# thermostat.net
KiCad netlist of a schematic drawn in EAGLE
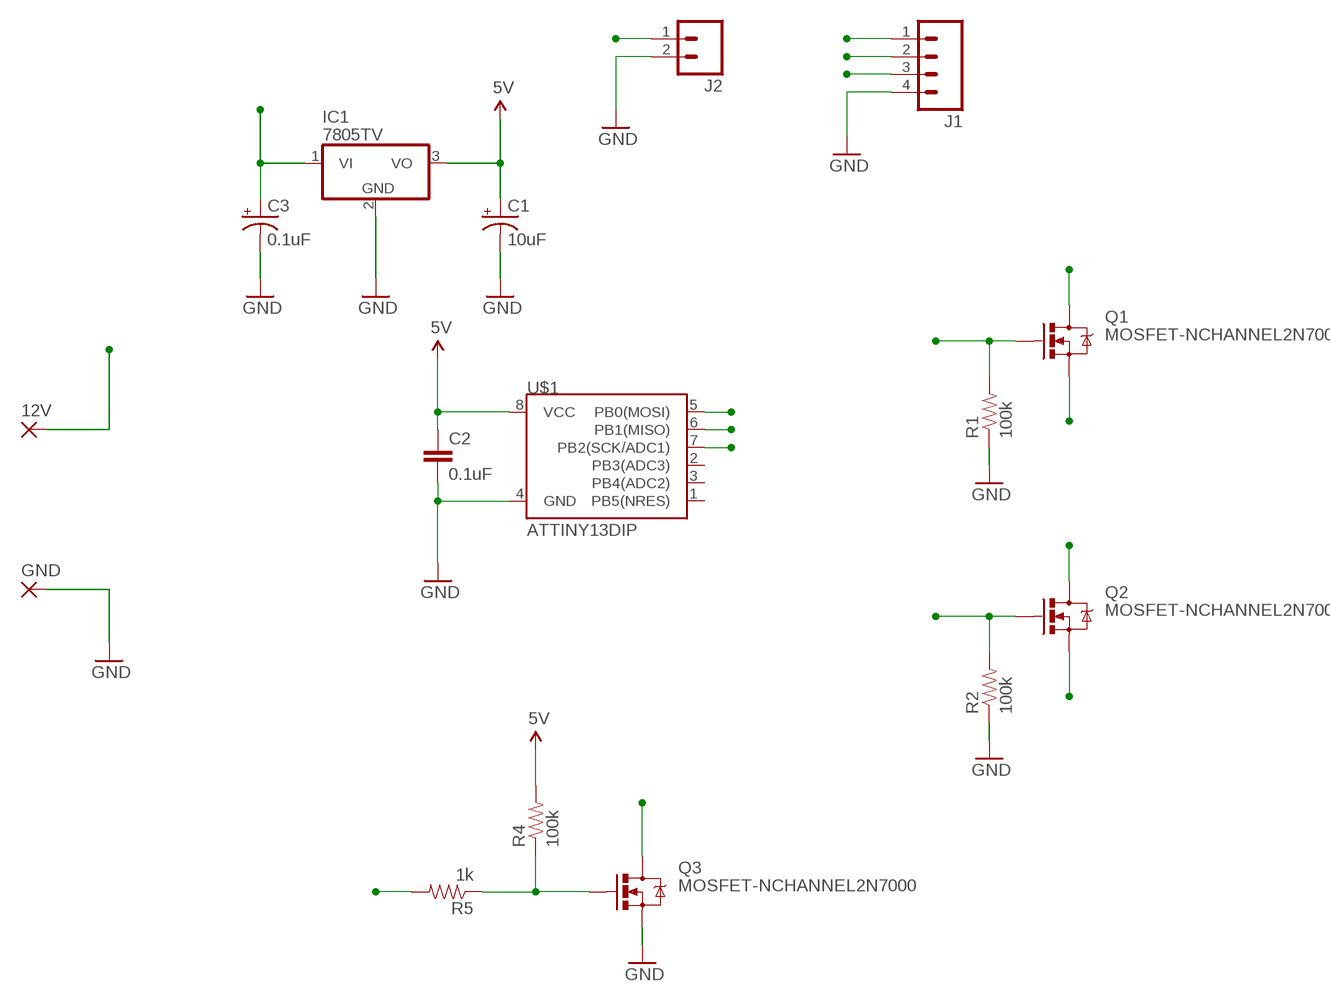
[diagram p0: schematic, sheet 1]

(export (version "E")
  (design (tool "Eeschema 10.0.6"))
  (components
    (comp (ref "12V")
      (value "WIREPAD2,54/0,8")
      (footprint "eagle-import:2,54_0,8")
      (libsource (lib "eagle-import") (part "WIREPAD2,54/0,8"))
    )
    (comp (ref "C1")
      (value "10uF")
      (footprint "eagle-import:CPOL-RADIAL-10UF-25V")
      (libsource (lib "eagle-import") (part "CAP_POLPTH2"))
    )
    (comp (ref "C2")
      (value "0.1uF")
      (footprint "eagle-import:CAP-PTH-SMALLEZ")
      (libsource (lib "eagle-import") (part "CAPEZ"))
    )
    (comp (ref "C3")
      (value "0.1uF")
      (footprint "eagle-import:CPOL-RADIAL-10UF-25V")
      (libsource (lib "eagle-import") (part "CAP_POLPTH2"))
    )
    (comp (ref "GND")
      (value "WIREPAD2,54/0,8")
      (footprint "eagle-import:2,54_0,8")
      (libsource (lib "eagle-import") (part "WIREPAD2,54/0,8"))
    )
    (comp (ref "IC1")
      (value "7805TV")
      (footprint "eagle-import:TO220V")
      (libsource (lib "eagle-import") (part "78TV05"))
    )
    (comp (ref "J1")
      (value "M04PTH")
      (footprint "eagle-import:1X04")
      (libsource (lib "eagle-import") (part "M04PTH"))
    )
    (comp (ref "J2")
      (value "M02PTH")
      (footprint "eagle-import:1X02")
      (libsource (lib "eagle-import") (part "M02PTH"))
    )
    (comp (ref "Q1")
      (value "MOSFET-NCHANNEL2N7000")
      (footprint "eagle-import:TO-92")
      (libsource (lib "eagle-import") (part "MOSFET-NCHANNEL2N7000"))
    )
    (comp (ref "Q2")
      (value "MOSFET-NCHANNEL2N7000")
      (footprint "eagle-import:TO-92")
      (libsource (lib "eagle-import") (part "MOSFET-NCHANNEL2N7000"))
    )
    (comp (ref "Q3")
      (value "MOSFET-NCHANNEL2N7000")
      (footprint "eagle-import:TO-92")
      (libsource (lib "eagle-import") (part "MOSFET-NCHANNEL2N7000"))
    )
    (comp (ref "R1")
      (value "100k")
      (footprint "eagle-import:AXIAL-0.3")
      (libsource (lib "eagle-import") (part "RESISTORAXIAL-0.3"))
    )
    (comp (ref "R2")
      (value "100k")
      (footprint "eagle-import:AXIAL-0.3")
      (libsource (lib "eagle-import") (part "RESISTORAXIAL-0.3"))
    )
    (comp (ref "R4")
      (value "100k")
      (footprint "eagle-import:AXIAL-0.3")
      (libsource (lib "eagle-import") (part "RESISTORAXIAL-0.3"))
    )
    (comp (ref "R5")
      (value "1k")
      (footprint "eagle-import:AXIAL-0.3")
      (libsource (lib "eagle-import") (part "RESISTORAXIAL-0.3"))
    )
    (comp (ref "U$1")
      (value "ATTINY13DIP")
      (footprint "eagle-import:DIP08")
      (libsource (lib "eagle-import") (part "ATTINY13DIP"))
    )
  )
  (nets
    (net (code "1") (name "/12V") (class "Default")
      (node (ref "12V") (pin "1") (pinfunction "P_1") (pintype "passive"))
      (node (ref "C3") (pin "1") (pinfunction "+_1") (pintype "passive"))
      (node (ref "IC1") (pin "1") (pinfunction "VI_1") (pintype "input"))
    )
    (net (code "2") (name "/HEAT_OFF") (class "Default")
      (node (ref "Q2") (pin "2") (pinfunction "G_2") (pintype "passive"))
      (node (ref "R2") (pin "P$2") (pinfunction "2_P$2") (pintype "passive"))
      (node (ref "U$1") (pin "5") (pinfunction "PB0(MOSI)_5") (pintype "bidirectional"))
    )
    (net (code "3") (name "/HEAT_ON") (class "Default")
      (node (ref "Q1") (pin "2") (pinfunction "G_2") (pintype "passive"))
      (node (ref "R1") (pin "P$2") (pinfunction "2_P$2") (pintype "passive"))
      (node (ref "U$1") (pin "6") (pinfunction "PB1(MISO)_6") (pintype "bidirectional"))
    )
    (net (code "4") (name "/SENSOR_IN") (class "Default")
      (node (ref "Q3") (pin "3") (pinfunction "D_3") (pintype "passive"))
      (node (ref "U$1") (pin "7") (pinfunction "PB2(SCK/ADC1)_7") (pintype "bidirectional"))
    )
    (net (code "5") (name "/SWITCH_OFF") (class "Default")
      (node (ref "J1") (pin "1") (pinfunction "1_1") (pintype "passive"))
      (node (ref "Q2") (pin "1") (pinfunction "S_1") (pintype "passive"))
    )
    (net (code "6") (name "/SWITCH_ON") (class "Default")
      (node (ref "J1") (pin "2") (pinfunction "2_2") (pintype "passive"))
      (node (ref "Q1") (pin "1") (pinfunction "S_1") (pintype "passive"))
    )
    (net (code "7") (name "/SW_COMMON") (class "Default")
      (node (ref "J1") (pin "3") (pinfunction "3_3") (pintype "passive"))
      (node (ref "Q1") (pin "3") (pinfunction "D_3") (pintype "passive"))
      (node (ref "Q2") (pin "3") (pinfunction "D_3") (pintype "passive"))
    )
    (net (code "8") (name "/THERMOSTAT_IN") (class "Default")
      (node (ref "J2") (pin "1") (pinfunction "1_1") (pintype "passive"))
      (node (ref "R5") (pin "P$2") (pinfunction "2_P$2") (pintype "passive"))
    )
    (net (code "9") (name "5V") (class "Default")
      (node (ref "C1") (pin "1") (pinfunction "+_1") (pintype "passive"))
      (node (ref "C2") (pin "1") (pinfunction "1_1") (pintype "passive"))
      (node (ref "IC1") (pin "3") (pinfunction "VO_3") (pintype "passive"))
      (node (ref "R4") (pin "P$2") (pinfunction "2_P$2") (pintype "passive"))
      (node (ref "U$1") (pin "8") (pinfunction "VCC_8") (pintype "bidirectional"))
    )
    (net (code "10") (name "GND") (class "Default")
      (node (ref "C1") (pin "2") (pinfunction "-_2") (pintype "passive"))
      (node (ref "C2") (pin "2") (pinfunction "2_2") (pintype "passive"))
      (node (ref "C3") (pin "2") (pinfunction "-_2") (pintype "passive"))
      (node (ref "GND") (pin "1") (pinfunction "P_1") (pintype "passive"))
      (node (ref "IC1") (pin "2") (pinfunction "GND_2") (pintype "passive"))
      (node (ref "J1") (pin "4") (pinfunction "4_4") (pintype "passive"))
      (node (ref "J2") (pin "2") (pinfunction "2_2") (pintype "passive"))
      (node (ref "Q3") (pin "1") (pinfunction "S_1") (pintype "passive"))
      (node (ref "R1") (pin "P$1") (pinfunction "1_P$1") (pintype "passive"))
      (node (ref "R2") (pin "P$1") (pinfunction "1_P$1") (pintype "passive"))
      (node (ref "U$1") (pin "4") (pinfunction "GND_4") (pintype "bidirectional"))
    )
    (net (code "11") (name "Net-(Q3-G)") (class "Default")
      (node (ref "Q3") (pin "2") (pinfunction "G_2") (pintype "passive"))
      (node (ref "R4") (pin "P$1") (pinfunction "1_P$1") (pintype "passive"))
      (node (ref "R5") (pin "P$1") (pinfunction "1_P$1") (pintype "passive"))
    )
    (net (code "12") (name "unconnected-(U$1-PB3(ADC3)-Pad2)") (class "Default")
      (node (ref "U$1") (pin "2") (pinfunction "PB3(ADC3)_2") (pintype "bidirectional"))
    )
    (net (code "13") (name "unconnected-(U$1-PB4(ADC2)-Pad3)") (class "Default")
      (node (ref "U$1") (pin "3") (pinfunction "PB4(ADC2)_3") (pintype "bidirectional"))
    )
    (net (code "14") (name "unconnected-(U$1-PB5(NRES)-Pad1)") (class "Default")
      (node (ref "U$1") (pin "1") (pinfunction "PB5(NRES)_1") (pintype "bidirectional"))
    )
  )
)
